# 003-00006.net
KiCad netlist of a schematic drawn in Altium Designer
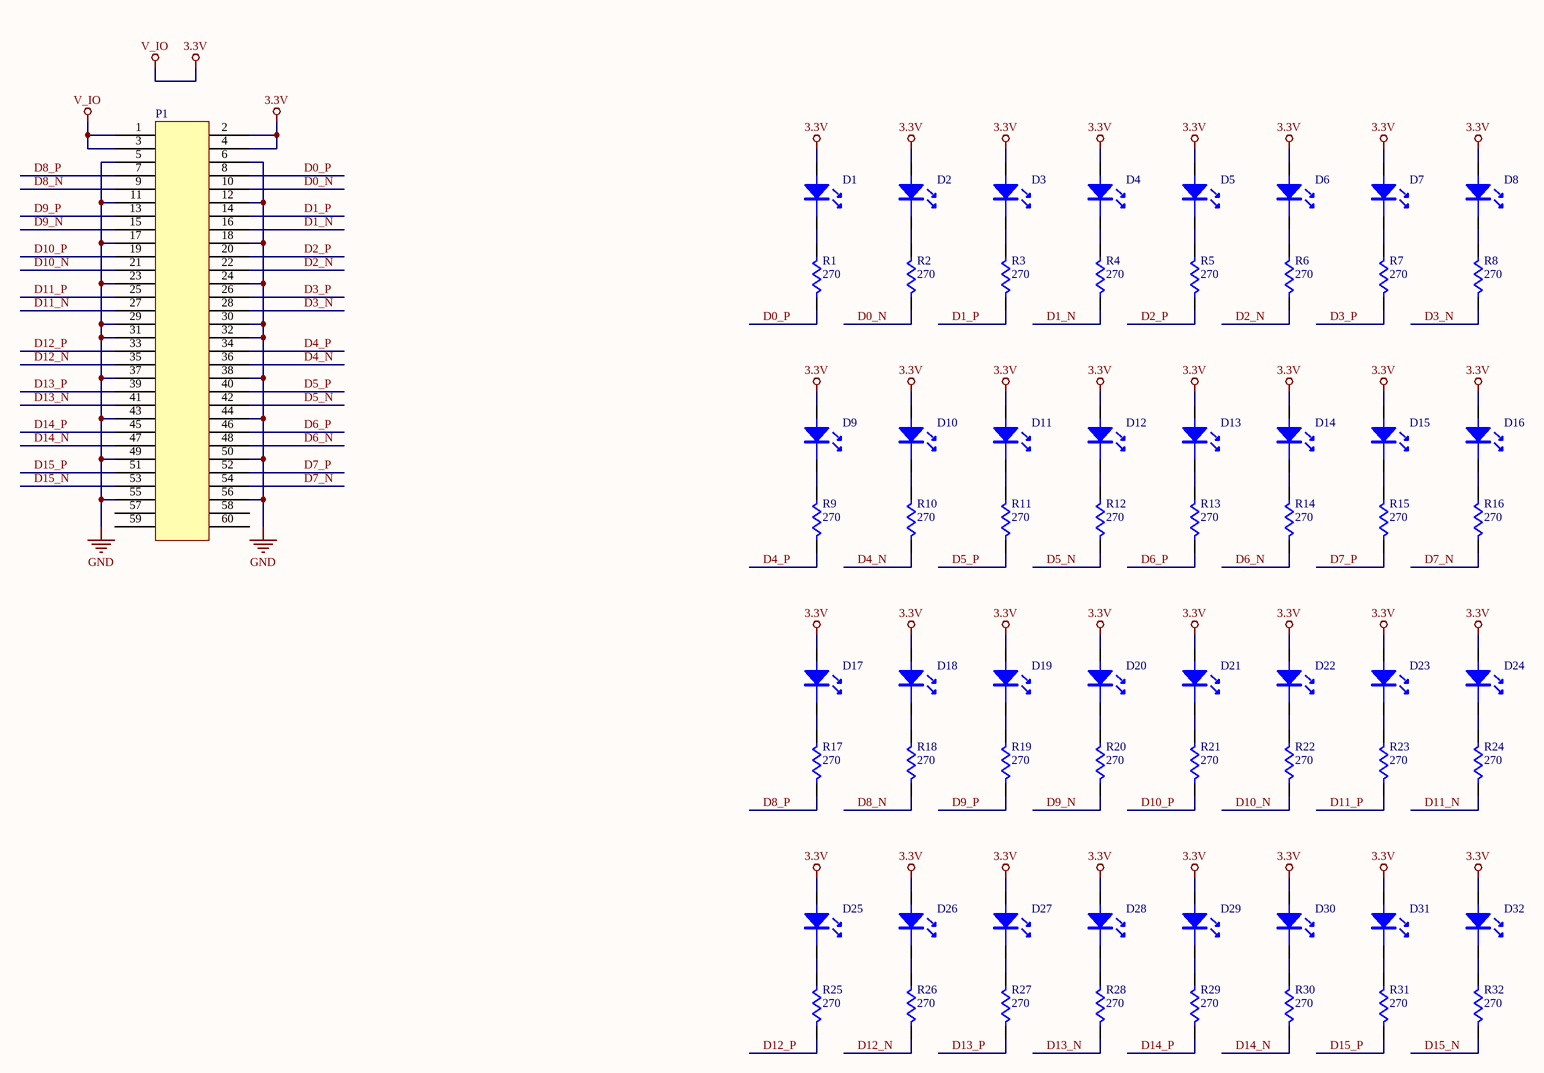
[diagram p0: 003-00006.SchDoc]

(export (version "E")
  (design (tool "Eeschema 10.0.6"))
  (components
    (comp (ref "D1")
      (value "~")
      (footprint "005-00018")
      (description "LED Green SMD 20mA 2.2V 0603")
      (fields (field (name "PART NUMBER") "013-00003") (field (name "VOLTAGE") "2.2V"))
      (libsource (lib "CES Component Library") (part "004-00016"))
    )
    (comp (ref "D2")
      (value "~")
      (footprint "005-00018")
      (description "LED Green SMD 20mA 2.2V 0603")
      (fields (field (name "PART NUMBER") "013-00003") (field (name "VOLTAGE") "2.2V"))
      (libsource (lib "CES Component Library") (part "004-00016"))
    )
    (comp (ref "D3")
      (value "~")
      (footprint "005-00018")
      (description "LED Green SMD 20mA 2.2V 0603")
      (fields (field (name "PART NUMBER") "013-00003") (field (name "VOLTAGE") "2.2V"))
      (libsource (lib "CES Component Library") (part "004-00016"))
    )
    (comp (ref "D4")
      (value "~")
      (footprint "005-00018")
      (description "LED Green SMD 20mA 2.2V 0603")
      (fields (field (name "PART NUMBER") "013-00003") (field (name "VOLTAGE") "2.2V"))
      (libsource (lib "CES Component Library") (part "004-00016"))
    )
    (comp (ref "D5")
      (value "~")
      (footprint "005-00018")
      (description "LED Green SMD 20mA 2.2V 0603")
      (fields (field (name "PART NUMBER") "013-00003") (field (name "VOLTAGE") "2.2V"))
      (libsource (lib "CES Component Library") (part "004-00016"))
    )
    (comp (ref "D6")
      (value "~")
      (footprint "005-00018")
      (description "LED Green SMD 20mA 2.2V 0603")
      (fields (field (name "PART NUMBER") "013-00003") (field (name "VOLTAGE") "2.2V"))
      (libsource (lib "CES Component Library") (part "004-00016"))
    )
    (comp (ref "D7")
      (value "~")
      (footprint "005-00018")
      (description "LED Green SMD 20mA 2.2V 0603")
      (fields (field (name "PART NUMBER") "013-00003") (field (name "VOLTAGE") "2.2V"))
      (libsource (lib "CES Component Library") (part "004-00016"))
    )
    (comp (ref "D8")
      (value "~")
      (footprint "005-00018")
      (description "LED Green SMD 20mA 2.2V 0603")
      (fields (field (name "PART NUMBER") "013-00003") (field (name "VOLTAGE") "2.2V"))
      (libsource (lib "CES Component Library") (part "004-00016"))
    )
    (comp (ref "D9")
      (value "~")
      (footprint "005-00018")
      (description "LED Green SMD 20mA 2.2V 0603")
      (fields (field (name "PART NUMBER") "013-00003") (field (name "VOLTAGE") "2.2V"))
      (libsource (lib "CES Component Library") (part "004-00016"))
    )
    (comp (ref "D10")
      (value "~")
      (footprint "005-00018")
      (description "LED Green SMD 20mA 2.2V 0603")
      (fields (field (name "PART NUMBER") "013-00003") (field (name "VOLTAGE") "2.2V"))
      (libsource (lib "CES Component Library") (part "004-00016"))
    )
    (comp (ref "D11")
      (value "~")
      (footprint "005-00018")
      (description "LED Green SMD 20mA 2.2V 0603")
      (fields (field (name "PART NUMBER") "013-00003") (field (name "VOLTAGE") "2.2V"))
      (libsource (lib "CES Component Library") (part "004-00016"))
    )
    (comp (ref "D12")
      (value "~")
      (footprint "005-00018")
      (description "LED Green SMD 20mA 2.2V 0603")
      (fields (field (name "PART NUMBER") "013-00003") (field (name "VOLTAGE") "2.2V"))
      (libsource (lib "CES Component Library") (part "004-00016"))
    )
    (comp (ref "D13")
      (value "~")
      (footprint "005-00018")
      (description "LED Green SMD 20mA 2.2V 0603")
      (fields (field (name "PART NUMBER") "013-00003") (field (name "VOLTAGE") "2.2V"))
      (libsource (lib "CES Component Library") (part "004-00016"))
    )
    (comp (ref "D14")
      (value "~")
      (footprint "005-00018")
      (description "LED Green SMD 20mA 2.2V 0603")
      (fields (field (name "PART NUMBER") "013-00003") (field (name "VOLTAGE") "2.2V"))
      (libsource (lib "CES Component Library") (part "004-00016"))
    )
    (comp (ref "D15")
      (value "~")
      (footprint "005-00018")
      (description "LED Green SMD 20mA 2.2V 0603")
      (fields (field (name "PART NUMBER") "013-00003") (field (name "VOLTAGE") "2.2V"))
      (libsource (lib "CES Component Library") (part "004-00016"))
    )
    (comp (ref "D16")
      (value "~")
      (footprint "005-00018")
      (description "LED Green SMD 20mA 2.2V 0603")
      (fields (field (name "PART NUMBER") "013-00003") (field (name "VOLTAGE") "2.2V"))
      (libsource (lib "CES Component Library") (part "004-00016"))
    )
    (comp (ref "D17")
      (value "~")
      (footprint "005-00018")
      (description "LED Green SMD 20mA 2.2V 0603")
      (fields (field (name "PART NUMBER") "013-00003") (field (name "VOLTAGE") "2.2V"))
      (libsource (lib "CES Component Library") (part "004-00016"))
    )
    (comp (ref "D18")
      (value "~")
      (footprint "005-00018")
      (description "LED Green SMD 20mA 2.2V 0603")
      (fields (field (name "PART NUMBER") "013-00003") (field (name "VOLTAGE") "2.2V"))
      (libsource (lib "CES Component Library") (part "004-00016"))
    )
    (comp (ref "D19")
      (value "~")
      (footprint "005-00018")
      (description "LED Green SMD 20mA 2.2V 0603")
      (fields (field (name "PART NUMBER") "013-00003") (field (name "VOLTAGE") "2.2V"))
      (libsource (lib "CES Component Library") (part "004-00016"))
    )
    (comp (ref "D20")
      (value "~")
      (footprint "005-00018")
      (description "LED Green SMD 20mA 2.2V 0603")
      (fields (field (name "PART NUMBER") "013-00003") (field (name "VOLTAGE") "2.2V"))
      (libsource (lib "CES Component Library") (part "004-00016"))
    )
    (comp (ref "D21")
      (value "~")
      (footprint "005-00018")
      (description "LED Green SMD 20mA 2.2V 0603")
      (fields (field (name "PART NUMBER") "013-00003") (field (name "VOLTAGE") "2.2V"))
      (libsource (lib "CES Component Library") (part "004-00016"))
    )
    (comp (ref "D22")
      (value "~")
      (footprint "005-00018")
      (description "LED Green SMD 20mA 2.2V 0603")
      (fields (field (name "PART NUMBER") "013-00003") (field (name "VOLTAGE") "2.2V"))
      (libsource (lib "CES Component Library") (part "004-00016"))
    )
    (comp (ref "D23")
      (value "~")
      (footprint "005-00018")
      (description "LED Green SMD 20mA 2.2V 0603")
      (fields (field (name "PART NUMBER") "013-00003") (field (name "VOLTAGE") "2.2V"))
      (libsource (lib "CES Component Library") (part "004-00016"))
    )
    (comp (ref "D24")
      (value "~")
      (footprint "005-00018")
      (description "LED Green SMD 20mA 2.2V 0603")
      (fields (field (name "PART NUMBER") "013-00003") (field (name "VOLTAGE") "2.2V"))
      (libsource (lib "CES Component Library") (part "004-00016"))
    )
    (comp (ref "D25")
      (value "~")
      (footprint "005-00018")
      (description "LED Green SMD 20mA 2.2V 0603")
      (fields (field (name "PART NUMBER") "013-00003") (field (name "VOLTAGE") "2.2V"))
      (libsource (lib "CES Component Library") (part "004-00016"))
    )
    (comp (ref "D26")
      (value "~")
      (footprint "005-00018")
      (description "LED Green SMD 20mA 2.2V 0603")
      (fields (field (name "PART NUMBER") "013-00003") (field (name "VOLTAGE") "2.2V"))
      (libsource (lib "CES Component Library") (part "004-00016"))
    )
    (comp (ref "D27")
      (value "~")
      (footprint "005-00018")
      (description "LED Green SMD 20mA 2.2V 0603")
      (fields (field (name "PART NUMBER") "013-00003") (field (name "VOLTAGE") "2.2V"))
      (libsource (lib "CES Component Library") (part "004-00016"))
    )
    (comp (ref "D28")
      (value "~")
      (footprint "005-00018")
      (description "LED Green SMD 20mA 2.2V 0603")
      (fields (field (name "PART NUMBER") "013-00003") (field (name "VOLTAGE") "2.2V"))
      (libsource (lib "CES Component Library") (part "004-00016"))
    )
    (comp (ref "D29")
      (value "~")
      (footprint "005-00018")
      (description "LED Green SMD 20mA 2.2V 0603")
      (fields (field (name "PART NUMBER") "013-00003") (field (name "VOLTAGE") "2.2V"))
      (libsource (lib "CES Component Library") (part "004-00016"))
    )
    (comp (ref "D30")
      (value "~")
      (footprint "005-00018")
      (description "LED Green SMD 20mA 2.2V 0603")
      (fields (field (name "PART NUMBER") "013-00003") (field (name "VOLTAGE") "2.2V"))
      (libsource (lib "CES Component Library") (part "004-00016"))
    )
    (comp (ref "D31")
      (value "~")
      (footprint "005-00018")
      (description "LED Green SMD 20mA 2.2V 0603")
      (fields (field (name "PART NUMBER") "013-00003") (field (name "VOLTAGE") "2.2V"))
      (libsource (lib "CES Component Library") (part "004-00016"))
    )
    (comp (ref "D32")
      (value "~")
      (footprint "005-00018")
      (description "LED Green SMD 20mA 2.2V 0603")
      (fields (field (name "PART NUMBER") "013-00003") (field (name "VOLTAGE") "2.2V"))
      (libsource (lib "CES Component Library") (part "004-00016"))
    )
    (comp (ref "P1")
      (value "~")
      (footprint "005-00024")
      (description "Connector, PCB edge, MEC8, 30x2 Pin")
      (fields (field (name "PART NUMBER") "008-00005"))
      (libsource (lib "CES Component Library") (part "004-00022"))
    )
    (comp (ref "R1")
      (value "270")
      (footprint "005-00009")
      (description "RES 270 OHM 1/16W 5% 0402")
      (fields (field (name "PART NUMBER") "009-00022") (field (name "TOLERANCE") "0.05"))
      (libsource (lib "CES Component Library") (part "004-00008"))
    )
    (comp (ref "R2")
      (value "270")
      (footprint "005-00009")
      (description "RES 270 OHM 1/16W 5% 0402")
      (fields (field (name "PART NUMBER") "009-00022") (field (name "TOLERANCE") "0.05"))
      (libsource (lib "CES Component Library") (part "004-00008"))
    )
    (comp (ref "R3")
      (value "270")
      (footprint "005-00009")
      (description "RES 270 OHM 1/16W 5% 0402")
      (fields (field (name "PART NUMBER") "009-00022") (field (name "TOLERANCE") "0.05"))
      (libsource (lib "CES Component Library") (part "004-00008"))
    )
    (comp (ref "R4")
      (value "270")
      (footprint "005-00009")
      (description "RES 270 OHM 1/16W 5% 0402")
      (fields (field (name "PART NUMBER") "009-00022") (field (name "TOLERANCE") "0.05"))
      (libsource (lib "CES Component Library") (part "004-00008"))
    )
    (comp (ref "R5")
      (value "270")
      (footprint "005-00009")
      (description "RES 270 OHM 1/16W 5% 0402")
      (fields (field (name "PART NUMBER") "009-00022") (field (name "TOLERANCE") "0.05"))
      (libsource (lib "CES Component Library") (part "004-00008"))
    )
    (comp (ref "R6")
      (value "270")
      (footprint "005-00009")
      (description "RES 270 OHM 1/16W 5% 0402")
      (fields (field (name "PART NUMBER") "009-00022") (field (name "TOLERANCE") "0.05"))
      (libsource (lib "CES Component Library") (part "004-00008"))
    )
    (comp (ref "R7")
      (value "270")
      (footprint "005-00009")
      (description "RES 270 OHM 1/16W 5% 0402")
      (fields (field (name "PART NUMBER") "009-00022") (field (name "TOLERANCE") "0.05"))
      (libsource (lib "CES Component Library") (part "004-00008"))
    )
    (comp (ref "R8")
      (value "270")
      (footprint "005-00009")
      (description "RES 270 OHM 1/16W 5% 0402")
      (fields (field (name "PART NUMBER") "009-00022") (field (name "TOLERANCE") "0.05"))
      (libsource (lib "CES Component Library") (part "004-00008"))
    )
    (comp (ref "R9")
      (value "270")
      (footprint "005-00009")
      (description "RES 270 OHM 1/16W 5% 0402")
      (fields (field (name "PART NUMBER") "009-00022") (field (name "TOLERANCE") "0.05"))
      (libsource (lib "CES Component Library") (part "004-00008"))
    )
    (comp (ref "R10")
      (value "270")
      (footprint "005-00009")
      (description "RES 270 OHM 1/16W 5% 0402")
      (fields (field (name "PART NUMBER") "009-00022") (field (name "TOLERANCE") "0.05"))
      (libsource (lib "CES Component Library") (part "004-00008"))
    )
    (comp (ref "R11")
      (value "270")
      (footprint "005-00009")
      (description "RES 270 OHM 1/16W 5% 0402")
      (fields (field (name "PART NUMBER") "009-00022") (field (name "TOLERANCE") "0.05"))
      (libsource (lib "CES Component Library") (part "004-00008"))
    )
    (comp (ref "R12")
      (value "270")
      (footprint "005-00009")
      (description "RES 270 OHM 1/16W 5% 0402")
      (fields (field (name "PART NUMBER") "009-00022") (field (name "TOLERANCE") "0.05"))
      (libsource (lib "CES Component Library") (part "004-00008"))
    )
    (comp (ref "R13")
      (value "270")
      (footprint "005-00009")
      (description "RES 270 OHM 1/16W 5% 0402")
      (fields (field (name "PART NUMBER") "009-00022") (field (name "TOLERANCE") "0.05"))
      (libsource (lib "CES Component Library") (part "004-00008"))
    )
    (comp (ref "R14")
      (value "270")
      (footprint "005-00009")
      (description "RES 270 OHM 1/16W 5% 0402")
      (fields (field (name "PART NUMBER") "009-00022") (field (name "TOLERANCE") "0.05"))
      (libsource (lib "CES Component Library") (part "004-00008"))
    )
    (comp (ref "R15")
      (value "270")
      (footprint "005-00009")
      (description "RES 270 OHM 1/16W 5% 0402")
      (fields (field (name "PART NUMBER") "009-00022") (field (name "TOLERANCE") "0.05"))
      (libsource (lib "CES Component Library") (part "004-00008"))
    )
    (comp (ref "R16")
      (value "270")
      (footprint "005-00009")
      (description "RES 270 OHM 1/16W 5% 0402")
      (fields (field (name "PART NUMBER") "009-00022") (field (name "TOLERANCE") "0.05"))
      (libsource (lib "CES Component Library") (part "004-00008"))
    )
    (comp (ref "R17")
      (value "270")
      (footprint "005-00009")
      (description "RES 270 OHM 1/16W 5% 0402")
      (fields (field (name "PART NUMBER") "009-00022") (field (name "TOLERANCE") "0.05"))
      (libsource (lib "CES Component Library") (part "004-00008"))
    )
    (comp (ref "R18")
      (value "270")
      (footprint "005-00009")
      (description "RES 270 OHM 1/16W 5% 0402")
      (fields (field (name "PART NUMBER") "009-00022") (field (name "TOLERANCE") "0.05"))
      (libsource (lib "CES Component Library") (part "004-00008"))
    )
    (comp (ref "R19")
      (value "270")
      (footprint "005-00009")
      (description "RES 270 OHM 1/16W 5% 0402")
      (fields (field (name "PART NUMBER") "009-00022") (field (name "TOLERANCE") "0.05"))
      (libsource (lib "CES Component Library") (part "004-00008"))
    )
    (comp (ref "R20")
      (value "270")
      (footprint "005-00009")
      (description "RES 270 OHM 1/16W 5% 0402")
      (fields (field (name "PART NUMBER") "009-00022") (field (name "TOLERANCE") "0.05"))
      (libsource (lib "CES Component Library") (part "004-00008"))
    )
    (comp (ref "R21")
      (value "270")
      (footprint "005-00009")
      (description "RES 270 OHM 1/16W 5% 0402")
      (fields (field (name "PART NUMBER") "009-00022") (field (name "TOLERANCE") "0.05"))
      (libsource (lib "CES Component Library") (part "004-00008"))
    )
    (comp (ref "R22")
      (value "270")
      (footprint "005-00009")
      (description "RES 270 OHM 1/16W 5% 0402")
      (fields (field (name "PART NUMBER") "009-00022") (field (name "TOLERANCE") "0.05"))
      (libsource (lib "CES Component Library") (part "004-00008"))
    )
    (comp (ref "R23")
      (value "270")
      (footprint "005-00009")
      (description "RES 270 OHM 1/16W 5% 0402")
      (fields (field (name "PART NUMBER") "009-00022") (field (name "TOLERANCE") "0.05"))
      (libsource (lib "CES Component Library") (part "004-00008"))
    )
    (comp (ref "R24")
      (value "270")
      (footprint "005-00009")
      (description "RES 270 OHM 1/16W 5% 0402")
      (fields (field (name "PART NUMBER") "009-00022") (field (name "TOLERANCE") "0.05"))
      (libsource (lib "CES Component Library") (part "004-00008"))
    )
    (comp (ref "R25")
      (value "270")
      (footprint "005-00009")
      (description "RES 270 OHM 1/16W 5% 0402")
      (fields (field (name "PART NUMBER") "009-00022") (field (name "TOLERANCE") "0.05"))
      (libsource (lib "CES Component Library") (part "004-00008"))
    )
    (comp (ref "R26")
      (value "270")
      (footprint "005-00009")
      (description "RES 270 OHM 1/16W 5% 0402")
      (fields (field (name "PART NUMBER") "009-00022") (field (name "TOLERANCE") "0.05"))
      (libsource (lib "CES Component Library") (part "004-00008"))
    )
    (comp (ref "R27")
      (value "270")
      (footprint "005-00009")
      (description "RES 270 OHM 1/16W 5% 0402")
      (fields (field (name "PART NUMBER") "009-00022") (field (name "TOLERANCE") "0.05"))
      (libsource (lib "CES Component Library") (part "004-00008"))
    )
    (comp (ref "R28")
      (value "270")
      (footprint "005-00009")
      (description "RES 270 OHM 1/16W 5% 0402")
      (fields (field (name "PART NUMBER") "009-00022") (field (name "TOLERANCE") "0.05"))
      (libsource (lib "CES Component Library") (part "004-00008"))
    )
    (comp (ref "R29")
      (value "270")
      (footprint "005-00009")
      (description "RES 270 OHM 1/16W 5% 0402")
      (fields (field (name "PART NUMBER") "009-00022") (field (name "TOLERANCE") "0.05"))
      (libsource (lib "CES Component Library") (part "004-00008"))
    )
    (comp (ref "R30")
      (value "270")
      (footprint "005-00009")
      (description "RES 270 OHM 1/16W 5% 0402")
      (fields (field (name "PART NUMBER") "009-00022") (field (name "TOLERANCE") "0.05"))
      (libsource (lib "CES Component Library") (part "004-00008"))
    )
    (comp (ref "R31")
      (value "270")
      (footprint "005-00009")
      (description "RES 270 OHM 1/16W 5% 0402")
      (fields (field (name "PART NUMBER") "009-00022") (field (name "TOLERANCE") "0.05"))
      (libsource (lib "CES Component Library") (part "004-00008"))
    )
    (comp (ref "R32")
      (value "270")
      (footprint "005-00009")
      (description "RES 270 OHM 1/16W 5% 0402")
      (fields (field (name "PART NUMBER") "009-00022") (field (name "TOLERANCE") "0.05"))
      (libsource (lib "CES Component Library") (part "004-00008"))
    )
  )
  (nets
    (net (code "1") (name "/D0_N") (class "Default")
      (node (ref "P1") (pin "10") (pinfunction "10_10") (pintype "passive"))
      (node (ref "R2") (pin "2") (pinfunction "2_2") (pintype "passive"))
    )
    (net (code "2") (name "/D0_P") (class "Default")
      (node (ref "P1") (pin "8") (pinfunction "8_8") (pintype "passive"))
      (node (ref "R1") (pin "2") (pinfunction "2_2") (pintype "passive"))
    )
    (net (code "3") (name "/D1_N") (class "Default")
      (node (ref "P1") (pin "16") (pinfunction "16_16") (pintype "passive"))
      (node (ref "R4") (pin "2") (pinfunction "2_2") (pintype "passive"))
    )
    (net (code "4") (name "/D1_P") (class "Default")
      (node (ref "P1") (pin "14") (pinfunction "14_14") (pintype "passive"))
      (node (ref "R3") (pin "2") (pinfunction "2_2") (pintype "passive"))
    )
    (net (code "5") (name "/D2_N") (class "Default")
      (node (ref "P1") (pin "22") (pinfunction "22_22") (pintype "passive"))
      (node (ref "R6") (pin "2") (pinfunction "2_2") (pintype "passive"))
    )
    (net (code "6") (name "/D2_P") (class "Default")
      (node (ref "P1") (pin "20") (pinfunction "20_20") (pintype "passive"))
      (node (ref "R5") (pin "2") (pinfunction "2_2") (pintype "passive"))
    )
    (net (code "7") (name "/D3_N") (class "Default")
      (node (ref "P1") (pin "28") (pinfunction "28_28") (pintype "passive"))
      (node (ref "R8") (pin "2") (pinfunction "2_2") (pintype "passive"))
    )
    (net (code "8") (name "/D3_P") (class "Default")
      (node (ref "P1") (pin "26") (pinfunction "26_26") (pintype "passive"))
      (node (ref "R7") (pin "2") (pinfunction "2_2") (pintype "passive"))
    )
    (net (code "9") (name "/D4_N") (class "Default")
      (node (ref "P1") (pin "36") (pinfunction "36_36") (pintype "passive"))
      (node (ref "R10") (pin "2") (pinfunction "2_2") (pintype "passive"))
    )
    (net (code "10") (name "/D4_P") (class "Default")
      (node (ref "P1") (pin "34") (pinfunction "34_34") (pintype "passive"))
      (node (ref "R9") (pin "2") (pinfunction "2_2") (pintype "passive"))
    )
    (net (code "11") (name "/D5_N") (class "Default")
      (node (ref "P1") (pin "42") (pinfunction "42_42") (pintype "passive"))
      (node (ref "R12") (pin "2") (pinfunction "2_2") (pintype "passive"))
    )
    (net (code "12") (name "/D5_P") (class "Default")
      (node (ref "P1") (pin "40") (pinfunction "40_40") (pintype "passive"))
      (node (ref "R11") (pin "2") (pinfunction "2_2") (pintype "passive"))
    )
    (net (code "13") (name "/D6_N") (class "Default")
      (node (ref "P1") (pin "48") (pinfunction "48_48") (pintype "passive"))
      (node (ref "R14") (pin "2") (pinfunction "2_2") (pintype "passive"))
    )
    (net (code "14") (name "/D6_P") (class "Default")
      (node (ref "P1") (pin "46") (pinfunction "46_46") (pintype "passive"))
      (node (ref "R13") (pin "2") (pinfunction "2_2") (pintype "passive"))
    )
    (net (code "15") (name "/D7_N") (class "Default")
      (node (ref "P1") (pin "54") (pinfunction "54_54") (pintype "passive"))
      (node (ref "R16") (pin "2") (pinfunction "2_2") (pintype "passive"))
    )
    (net (code "16") (name "/D7_P") (class "Default")
      (node (ref "P1") (pin "52") (pinfunction "52_52") (pintype "passive"))
      (node (ref "R15") (pin "2") (pinfunction "2_2") (pintype "passive"))
    )
    (net (code "17") (name "/D8_N") (class "Default")
      (node (ref "P1") (pin "9") (pinfunction "9_9") (pintype "passive"))
      (node (ref "R18") (pin "2") (pinfunction "2_2") (pintype "passive"))
    )
    (net (code "18") (name "/D8_P") (class "Default")
      (node (ref "P1") (pin "7") (pinfunction "7_7") (pintype "passive"))
      (node (ref "R17") (pin "2") (pinfunction "2_2") (pintype "passive"))
    )
    (net (code "19") (name "/D9_N") (class "Default")
      (node (ref "P1") (pin "15") (pinfunction "15_15") (pintype "passive"))
      (node (ref "R20") (pin "2") (pinfunction "2_2") (pintype "passive"))
    )
    (net (code "20") (name "/D9_P") (class "Default")
      (node (ref "P1") (pin "13") (pinfunction "13_13") (pintype "passive"))
      (node (ref "R19") (pin "2") (pinfunction "2_2") (pintype "passive"))
    )
    (net (code "21") (name "/D10_N") (class "Default")
      (node (ref "P1") (pin "21") (pinfunction "21_21") (pintype "passive"))
      (node (ref "R22") (pin "2") (pinfunction "2_2") (pintype "passive"))
    )
    (net (code "22") (name "/D10_P") (class "Default")
      (node (ref "P1") (pin "19") (pinfunction "19_19") (pintype "passive"))
      (node (ref "R21") (pin "2") (pinfunction "2_2") (pintype "passive"))
    )
    (net (code "23") (name "/D11_N") (class "Default")
      (node (ref "P1") (pin "27") (pinfunction "27_27") (pintype "passive"))
      (node (ref "R24") (pin "2") (pinfunction "2_2") (pintype "passive"))
    )
    (net (code "24") (name "/D11_P") (class "Default")
      (node (ref "P1") (pin "25") (pinfunction "25_25") (pintype "passive"))
      (node (ref "R23") (pin "2") (pinfunction "2_2") (pintype "passive"))
    )
    (net (code "25") (name "/D12_N") (class "Default")
      (node (ref "P1") (pin "35") (pinfunction "35_35") (pintype "passive"))
      (node (ref "R26") (pin "2") (pinfunction "2_2") (pintype "passive"))
    )
    (net (code "26") (name "/D12_P") (class "Default")
      (node (ref "P1") (pin "33") (pinfunction "33_33") (pintype "passive"))
      (node (ref "R25") (pin "2") (pinfunction "2_2") (pintype "passive"))
    )
    (net (code "27") (name "/D13_N") (class "Default")
      (node (ref "P1") (pin "41") (pinfunction "41_41") (pintype "passive"))
      (node (ref "R28") (pin "2") (pinfunction "2_2") (pintype "passive"))
    )
    (net (code "28") (name "/D13_P") (class "Default")
      (node (ref "P1") (pin "39") (pinfunction "39_39") (pintype "passive"))
      (node (ref "R27") (pin "2") (pinfunction "2_2") (pintype "passive"))
    )
    (net (code "29") (name "/D14_N") (class "Default")
      (node (ref "P1") (pin "47") (pinfunction "47_47") (pintype "passive"))
      (node (ref "R30") (pin "2") (pinfunction "2_2") (pintype "passive"))
    )
    (net (code "30") (name "/D14_P") (class "Default")
      (node (ref "P1") (pin "45") (pinfunction "45_45") (pintype "passive"))
      (node (ref "R29") (pin "2") (pinfunction "2_2") (pintype "passive"))
    )
    (net (code "31") (name "/D15_N") (class "Default")
      (node (ref "P1") (pin "53") (pinfunction "53_53") (pintype "passive"))
      (node (ref "R32") (pin "2") (pinfunction "2_2") (pintype "passive"))
    )
    (net (code "32") (name "/D15_P") (class "Default")
      (node (ref "P1") (pin "51") (pinfunction "51_51") (pintype "passive"))
      (node (ref "R31") (pin "2") (pinfunction "2_2") (pintype "passive"))
    )
    (net (code "33") (name "3.3V") (class "Default")
      (node (ref "D1") (pin "ANODE") (pinfunction "ANODE_ANODE") (pintype "passive"))
      (node (ref "D10") (pin "ANODE") (pinfunction "ANODE_ANODE") (pintype "passive"))
      (node (ref "D11") (pin "ANODE") (pinfunction "ANODE_ANODE") (pintype "passive"))
      (node (ref "D12") (pin "ANODE") (pinfunction "ANODE_ANODE") (pintype "passive"))
      (node (ref "D13") (pin "ANODE") (pinfunction "ANODE_ANODE") (pintype "passive"))
      (node (ref "D14") (pin "ANODE") (pinfunction "ANODE_ANODE") (pintype "passive"))
      (node (ref "D15") (pin "ANODE") (pinfunction "ANODE_ANODE") (pintype "passive"))
      (node (ref "D16") (pin "ANODE") (pinfunction "ANODE_ANODE") (pintype "passive"))
      (node (ref "D17") (pin "ANODE") (pinfunction "ANODE_ANODE") (pintype "passive"))
      (node (ref "D18") (pin "ANODE") (pinfunction "ANODE_ANODE") (pintype "passive"))
      (node (ref "D19") (pin "ANODE") (pinfunction "ANODE_ANODE") (pintype "passive"))
      (node (ref "D2") (pin "ANODE") (pinfunction "ANODE_ANODE") (pintype "passive"))
      (node (ref "D20") (pin "ANODE") (pinfunction "ANODE_ANODE") (pintype "passive"))
      (node (ref "D21") (pin "ANODE") (pinfunction "ANODE_ANODE") (pintype "passive"))
      (node (ref "D22") (pin "ANODE") (pinfunction "ANODE_ANODE") (pintype "passive"))
      (node (ref "D23") (pin "ANODE") (pinfunction "ANODE_ANODE") (pintype "passive"))
      (node (ref "D24") (pin "ANODE") (pinfunction "ANODE_ANODE") (pintype "passive"))
      (node (ref "D25") (pin "ANODE") (pinfunction "ANODE_ANODE") (pintype "passive"))
      (node (ref "D26") (pin "ANODE") (pinfunction "ANODE_ANODE") (pintype "passive"))
      (node (ref "D27") (pin "ANODE") (pinfunction "ANODE_ANODE") (pintype "passive"))
      (node (ref "D28") (pin "ANODE") (pinfunction "ANODE_ANODE") (pintype "passive"))
      (node (ref "D29") (pin "ANODE") (pinfunction "ANODE_ANODE") (pintype "passive"))
      (node (ref "D3") (pin "ANODE") (pinfunction "ANODE_ANODE") (pintype "passive"))
      (node (ref "D30") (pin "ANODE") (pinfunction "ANODE_ANODE") (pintype "passive"))
      (node (ref "D31") (pin "ANODE") (pinfunction "ANODE_ANODE") (pintype "passive"))
      (node (ref "D32") (pin "ANODE") (pinfunction "ANODE_ANODE") (pintype "passive"))
      (node (ref "D4") (pin "ANODE") (pinfunction "ANODE_ANODE") (pintype "passive"))
      (node (ref "D5") (pin "ANODE") (pinfunction "ANODE_ANODE") (pintype "passive"))
      (node (ref "D6") (pin "ANODE") (pinfunction "ANODE_ANODE") (pintype "passive"))
      (node (ref "D7") (pin "ANODE") (pinfunction "ANODE_ANODE") (pintype "passive"))
      (node (ref "D8") (pin "ANODE") (pinfunction "ANODE_ANODE") (pintype "passive"))
      (node (ref "D9") (pin "ANODE") (pinfunction "ANODE_ANODE") (pintype "passive"))
      (node (ref "P1") (pin "1") (pinfunction "1_1") (pintype "passive"))
      (node (ref "P1") (pin "2") (pinfunction "2_2") (pintype "passive"))
      (node (ref "P1") (pin "3") (pinfunction "3_3") (pintype "passive"))
      (node (ref "P1") (pin "4") (pinfunction "4_4") (pintype "passive"))
    )
    (net (code "34") (name "GND") (class "Default")
      (node (ref "P1") (pin "11") (pinfunction "11_11") (pintype "passive"))
      (node (ref "P1") (pin "12") (pinfunction "12_12") (pintype "passive"))
      (node (ref "P1") (pin "17") (pinfunction "17_17") (pintype "passive"))
      (node (ref "P1") (pin "18") (pinfunction "18_18") (pintype "passive"))
      (node (ref "P1") (pin "23") (pinfunction "23_23") (pintype "passive"))
      (node (ref "P1") (pin "24") (pinfunction "24_24") (pintype "passive"))
      (node (ref "P1") (pin "29") (pinfunction "29_29") (pintype "passive"))
      (node (ref "P1") (pin "30") (pinfunction "30_30") (pintype "passive"))
      (node (ref "P1") (pin "31") (pinfunction "31_31") (pintype "passive"))
      (node (ref "P1") (pin "32") (pinfunction "32_32") (pintype "passive"))
      (node (ref "P1") (pin "37") (pinfunction "37_37") (pintype "passive"))
      (node (ref "P1") (pin "38") (pinfunction "38_38") (pintype "passive"))
      (node (ref "P1") (pin "43") (pinfunction "43_43") (pintype "passive"))
      (node (ref "P1") (pin "44") (pinfunction "44_44") (pintype "passive"))
      (node (ref "P1") (pin "49") (pinfunction "49_49") (pintype "passive"))
      (node (ref "P1") (pin "5") (pinfunction "5_5") (pintype "passive"))
      (node (ref "P1") (pin "50") (pinfunction "50_50") (pintype "passive"))
      (node (ref "P1") (pin "55") (pinfunction "55_55") (pintype "passive"))
      (node (ref "P1") (pin "56") (pinfunction "56_56") (pintype "passive"))
      (node (ref "P1") (pin "6") (pinfunction "6_6") (pintype "passive"))
    )
    (net (code "35") (name "Net-(D1-PadCATHODE)") (class "Default")
      (node (ref "D1") (pin "CATHODE") (pinfunction "CATHODE_CATHODE") (pintype "passive"))
      (node (ref "R1") (pin "1") (pinfunction "1_1") (pintype "passive"))
    )
    (net (code "36") (name "Net-(D2-PadCATHODE)") (class "Default")
      (node (ref "D2") (pin "CATHODE") (pinfunction "CATHODE_CATHODE") (pintype "passive"))
      (node (ref "R2") (pin "1") (pinfunction "1_1") (pintype "passive"))
    )
    (net (code "37") (name "Net-(D3-PadCATHODE)") (class "Default")
      (node (ref "D3") (pin "CATHODE") (pinfunction "CATHODE_CATHODE") (pintype "passive"))
      (node (ref "R3") (pin "1") (pinfunction "1_1") (pintype "passive"))
    )
    (net (code "38") (name "Net-(D4-PadCATHODE)") (class "Default")
      (node (ref "D4") (pin "CATHODE") (pinfunction "CATHODE_CATHODE") (pintype "passive"))
      (node (ref "R4") (pin "1") (pinfunction "1_1") (pintype "passive"))
    )
    (net (code "39") (name "Net-(D5-PadCATHODE)") (class "Default")
      (node (ref "D5") (pin "CATHODE") (pinfunction "CATHODE_CATHODE") (pintype "passive"))
      (node (ref "R5") (pin "1") (pinfunction "1_1") (pintype "passive"))
    )
    (net (code "40") (name "Net-(D6-PadCATHODE)") (class "Default")
      (node (ref "D6") (pin "CATHODE") (pinfunction "CATHODE_CATHODE") (pintype "passive"))
      (node (ref "R6") (pin "1") (pinfunction "1_1") (pintype "passive"))
    )
    (net (code "41") (name "Net-(D7-PadCATHODE)") (class "Default")
      (node (ref "D7") (pin "CATHODE") (pinfunction "CATHODE_CATHODE") (pintype "passive"))
      (node (ref "R7") (pin "1") (pinfunction "1_1") (pintype "passive"))
    )
    (net (code "42") (name "Net-(D8-PadCATHODE)") (class "Default")
      (node (ref "D8") (pin "CATHODE") (pinfunction "CATHODE_CATHODE") (pintype "passive"))
      (node (ref "R8") (pin "1") (pinfunction "1_1") (pintype "passive"))
    )
    (net (code "43") (name "Net-(D9-PadCATHODE)") (class "Default")
      (node (ref "D9") (pin "CATHODE") (pinfunction "CATHODE_CATHODE") (pintype "passive"))
      (node (ref "R9") (pin "1") (pinfunction "1_1") (pintype "passive"))
    )
    (net (code "44") (name "Net-(D10-PadCATHODE)") (class "Default")
      (node (ref "D10") (pin "CATHODE") (pinfunction "CATHODE_CATHODE") (pintype "passive"))
      (node (ref "R10") (pin "1") (pinfunction "1_1") (pintype "passive"))
    )
    (net (code "45") (name "Net-(D11-PadCATHODE)") (class "Default")
      (node (ref "D11") (pin "CATHODE") (pinfunction "CATHODE_CATHODE") (pintype "passive"))
      (node (ref "R11") (pin "1") (pinfunction "1_1") (pintype "passive"))
    )
    (net (code "46") (name "Net-(D12-PadCATHODE)") (class "Default")
      (node (ref "D12") (pin "CATHODE") (pinfunction "CATHODE_CATHODE") (pintype "passive"))
      (node (ref "R12") (pin "1") (pinfunction "1_1") (pintype "passive"))
    )
    (net (code "47") (name "Net-(D13-PadCATHODE)") (class "Default")
      (node (ref "D13") (pin "CATHODE") (pinfunction "CATHODE_CATHODE") (pintype "passive"))
      (node (ref "R13") (pin "1") (pinfunction "1_1") (pintype "passive"))
    )
    (net (code "48") (name "Net-(D14-PadCATHODE)") (class "Default")
      (node (ref "D14") (pin "CATHODE") (pinfunction "CATHODE_CATHODE") (pintype "passive"))
      (node (ref "R14") (pin "1") (pinfunction "1_1") (pintype "passive"))
    )
    (net (code "49") (name "Net-(D15-PadCATHODE)") (class "Default")
      (node (ref "D15") (pin "CATHODE") (pinfunction "CATHODE_CATHODE") (pintype "passive"))
      (node (ref "R15") (pin "1") (pinfunction "1_1") (pintype "passive"))
    )
    (net (code "50") (name "Net-(D16-PadCATHODE)") (class "Default")
      (node (ref "D16") (pin "CATHODE") (pinfunction "CATHODE_CATHODE") (pintype "passive"))
      (node (ref "R16") (pin "1") (pinfunction "1_1") (pintype "passive"))
    )
    (net (code "51") (name "Net-(D17-PadCATHODE)") (class "Default")
      (node (ref "D17") (pin "CATHODE") (pinfunction "CATHODE_CATHODE") (pintype "passive"))
      (node (ref "R17") (pin "1") (pinfunction "1_1") (pintype "passive"))
    )
    (net (code "52") (name "Net-(D18-PadCATHODE)") (class "Default")
      (node (ref "D18") (pin "CATHODE") (pinfunction "CATHODE_CATHODE") (pintype "passive"))
      (node (ref "R18") (pin "1") (pinfunction "1_1") (pintype "passive"))
    )
    (net (code "53") (name "Net-(D19-PadCATHODE)") (class "Default")
      (node (ref "D19") (pin "CATHODE") (pinfunction "CATHODE_CATHODE") (pintype "passive"))
      (node (ref "R19") (pin "1") (pinfunction "1_1") (pintype "passive"))
    )
    (net (code "54") (name "Net-(D20-PadCATHODE)") (class "Default")
      (node (ref "D20") (pin "CATHODE") (pinfunction "CATHODE_CATHODE") (pintype "passive"))
      (node (ref "R20") (pin "1") (pinfunction "1_1") (pintype "passive"))
    )
    (net (code "55") (name "Net-(D21-PadCATHODE)") (class "Default")
      (node (ref "D21") (pin "CATHODE") (pinfunction "CATHODE_CATHODE") (pintype "passive"))
      (node (ref "R21") (pin "1") (pinfunction "1_1") (pintype "passive"))
    )
    (net (code "56") (name "Net-(D22-PadCATHODE)") (class "Default")
      (node (ref "D22") (pin "CATHODE") (pinfunction "CATHODE_CATHODE") (pintype "passive"))
      (node (ref "R22") (pin "1") (pinfunction "1_1") (pintype "passive"))
    )
    (net (code "57") (name "Net-(D23-PadCATHODE)") (class "Default")
      (node (ref "D23") (pin "CATHODE") (pinfunction "CATHODE_CATHODE") (pintype "passive"))
      (node (ref "R23") (pin "1") (pinfunction "1_1") (pintype "passive"))
    )
    (net (code "58") (name "Net-(D24-PadCATHODE)") (class "Default")
      (node (ref "D24") (pin "CATHODE") (pinfunction "CATHODE_CATHODE") (pintype "passive"))
      (node (ref "R24") (pin "1") (pinfunction "1_1") (pintype "passive"))
    )
    (net (code "59") (name "Net-(D25-PadCATHODE)") (class "Default")
      (node (ref "D25") (pin "CATHODE") (pinfunction "CATHODE_CATHODE") (pintype "passive"))
      (node (ref "R25") (pin "1") (pinfunction "1_1") (pintype "passive"))
    )
    (net (code "60") (name "Net-(D26-PadCATHODE)") (class "Default")
      (node (ref "D26") (pin "CATHODE") (pinfunction "CATHODE_CATHODE") (pintype "passive"))
      (node (ref "R26") (pin "1") (pinfunction "1_1") (pintype "passive"))
    )
    (net (code "61") (name "Net-(D27-PadCATHODE)") (class "Default")
      (node (ref "D27") (pin "CATHODE") (pinfunction "CATHODE_CATHODE") (pintype "passive"))
      (node (ref "R27") (pin "1") (pinfunction "1_1") (pintype "passive"))
    )
    (net (code "62") (name "Net-(D28-PadCATHODE)") (class "Default")
      (node (ref "D28") (pin "CATHODE") (pinfunction "CATHODE_CATHODE") (pintype "passive"))
      (node (ref "R28") (pin "1") (pinfunction "1_1") (pintype "passive"))
    )
    (net (code "63") (name "Net-(D29-PadCATHODE)") (class "Default")
      (node (ref "D29") (pin "CATHODE") (pinfunction "CATHODE_CATHODE") (pintype "passive"))
      (node (ref "R29") (pin "1") (pinfunction "1_1") (pintype "passive"))
    )
    (net (code "64") (name "Net-(D30-PadCATHODE)") (class "Default")
      (node (ref "D30") (pin "CATHODE") (pinfunction "CATHODE_CATHODE") (pintype "passive"))
      (node (ref "R30") (pin "1") (pinfunction "1_1") (pintype "passive"))
    )
    (net (code "65") (name "Net-(D31-PadCATHODE)") (class "Default")
      (node (ref "D31") (pin "CATHODE") (pinfunction "CATHODE_CATHODE") (pintype "passive"))
      (node (ref "R31") (pin "1") (pinfunction "1_1") (pintype "passive"))
    )
    (net (code "66") (name "Net-(D32-PadCATHODE)") (class "Default")
      (node (ref "D32") (pin "CATHODE") (pinfunction "CATHODE_CATHODE") (pintype "passive"))
      (node (ref "R32") (pin "1") (pinfunction "1_1") (pintype "passive"))
    )
    (net (code "67") (name "unconnected-(P1-Pad57)") (class "Default")
      (node (ref "P1") (pin "57") (pinfunction "57_57") (pintype "passive"))
    )
    (net (code "68") (name "unconnected-(P1-Pad58)") (class "Default")
      (node (ref "P1") (pin "58") (pinfunction "58_58") (pintype "passive"))
    )
    (net (code "69") (name "unconnected-(P1-Pad59)") (class "Default")
      (node (ref "P1") (pin "59") (pinfunction "59_59") (pintype "passive"))
    )
    (net (code "70") (name "unconnected-(P1-Pad60)") (class "Default")
      (node (ref "P1") (pin "60") (pinfunction "60_60") (pintype "passive"))
    )
  )
)
